# design.net
KiCad netlist of a schematic drawn in Altium Designer
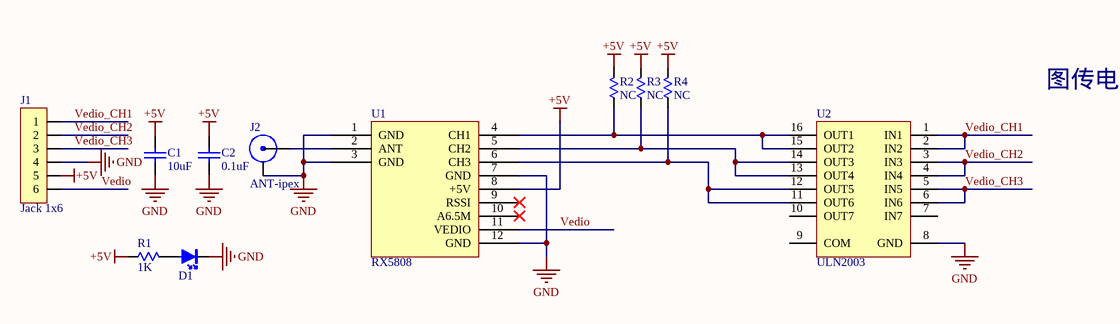
[diagram p0: 海关全向控制器图传转接板.SchDoc]

(export (version "E")
  (design (tool "Eeschema 10.0.6"))
  (components
    (comp (ref "C1") (value "10uF") (footprint "C0603") (libsource (lib "SMD") (part "Cap Semi")))
    (comp (ref "C2") (value "0.1uF") (footprint "C0603") (libsource (lib "SMD") (part "Cap Semi")))
    (comp (ref "D1")
      (value "LED")
      (footprint "LED0603")
      (libsource (lib "Passive Components Class") (part "LED"))
    )
    (comp (ref "J1")
      (value "Jack 1x6")
      (footprint "ZH-6AWD")
      (description "插座")
      (libsource (lib "Connector") (part "Jack 1x6"))
    )
    (comp (ref "J2") (value "ANT-ipex") (footprint "IPEX") (libsource (lib "RLCYDF") (part "ANT-ipex")))
    (comp (ref "R1")
      (value "1K")
      (footprint "R0603")
      (description "Resistor")
      (fields (field (name "PUBLISHER") "Altium Limited"))
      (libsource (lib "UP-Robot") (part "Res"))
    )
    (comp (ref "R2")
      (value "NC")
      (footprint "R0603")
      (description "Resistor")
      (fields (field (name "PUBLISHER") "Altium Limited"))
      (libsource (lib "UP-Robot") (part "Res"))
    )
    (comp (ref "R3")
      (value "NC")
      (footprint "R0603")
      (description "Resistor")
      (fields (field (name "PUBLISHER") "Altium Limited"))
      (libsource (lib "UP-Robot") (part "Res"))
    )
    (comp (ref "R4")
      (value "NC")
      (footprint "R0603")
      (description "Resistor")
      (fields (field (name "PUBLISHER") "Altium Limited"))
      (libsource (lib "UP-Robot") (part "Res"))
    )
    (comp (ref "U1") (value "RX5808") (footprint "RX5808") (libsource (lib "Module") (part "RX5808")))
    (comp (ref "U2") (value "ULN2003") (footprint "SO16") (libsource (lib "Logic Class") (part "ULN2003")))
  )
  (nets
    (net (code "1") (name "+5V") (class "Default")
      (node (ref "C1") (pin "2") (pinfunction "2_2") (pintype "passive"))
      (node (ref "C2") (pin "2") (pinfunction "2_2") (pintype "passive"))
      (node (ref "J1") (pin "5") (pinfunction "5_5") (pintype "passive"))
      (node (ref "R1") (pin "1") (pinfunction "1_1") (pintype "passive"))
      (node (ref "R2") (pin "2") (pinfunction "2_2") (pintype "passive"))
      (node (ref "R3") (pin "2") (pinfunction "2_2") (pintype "passive"))
      (node (ref "R4") (pin "2") (pinfunction "2_2") (pintype "passive"))
      (node (ref "U1") (pin "8") (pinfunction "+5V_8") (pintype "passive"))
    )
    (net (code "2") (name "/Vedio") (class "Default")
      (node (ref "J1") (pin "6") (pinfunction "6_6") (pintype "passive"))
      (node (ref "U1") (pin "11") (pinfunction "VEDIO_11") (pintype "passive"))
    )
    (net (code "3") (name "/Vedio_CH1") (class "Default")
      (node (ref "J1") (pin "1") (pinfunction "1_1") (pintype "passive"))
      (node (ref "U2") (pin "1") (pinfunction "IN1_1") (pintype "passive"))
      (node (ref "U2") (pin "2") (pinfunction "IN2_2") (pintype "passive"))
    )
    (net (code "4") (name "/Vedio_CH2") (class "Default")
      (node (ref "J1") (pin "2") (pinfunction "2_2") (pintype "passive"))
      (node (ref "U2") (pin "3") (pinfunction "IN3_3") (pintype "passive"))
      (node (ref "U2") (pin "4") (pinfunction "IN4_4") (pintype "passive"))
    )
    (net (code "5") (name "/Vedio_CH3") (class "Default")
      (node (ref "J1") (pin "3") (pinfunction "3_3") (pintype "passive"))
      (node (ref "U2") (pin "5") (pinfunction "IN5_5") (pintype "passive"))
      (node (ref "U2") (pin "6") (pinfunction "IN6_6") (pintype "passive"))
    )
    (net (code "6") (name "GND") (class "Default")
      (node (ref "C1") (pin "1") (pinfunction "1_1") (pintype "passive"))
      (node (ref "C2") (pin "1") (pinfunction "1_1") (pintype "passive"))
      (node (ref "D1") (pin "2") (pinfunction "K_2") (pintype "passive"))
      (node (ref "J1") (pin "4") (pinfunction "4_4") (pintype "passive"))
      (node (ref "J2") (pin "2") (pinfunction "GND_2") (pintype "passive"))
      (node (ref "U1") (pin "1") (pinfunction "GND_1") (pintype "passive"))
      (node (ref "U1") (pin "12") (pinfunction "GND_12") (pintype "passive"))
      (node (ref "U1") (pin "3") (pinfunction "GND_3") (pintype "passive"))
      (node (ref "U1") (pin "7") (pinfunction "GND_7") (pintype "passive"))
      (node (ref "U2") (pin "8") (pinfunction "GND_8") (pintype "power_in"))
    )
    (net (code "7") (name "Net-(D1-A)") (class "Default")
      (node (ref "D1") (pin "1") (pinfunction "A_1") (pintype "passive"))
      (node (ref "R1") (pin "2") (pinfunction "2_2") (pintype "passive"))
    )
    (net (code "8") (name "Net-(J2-ANT)") (class "Default")
      (node (ref "J2") (pin "1") (pinfunction "ANT_1") (pintype "passive"))
      (node (ref "U1") (pin "2") (pinfunction "ANT_2") (pintype "passive"))
    )
    (net (code "9") (name "Net-(U1-CH1)") (class "Default")
      (node (ref "R2") (pin "1") (pinfunction "1_1") (pintype "passive"))
      (node (ref "U1") (pin "4") (pinfunction "CH1_4") (pintype "passive"))
      (node (ref "U2") (pin "15") (pinfunction "OUT2_15") (pintype "open_collector"))
      (node (ref "U2") (pin "16") (pinfunction "OUT1_16") (pintype "open_collector"))
    )
    (net (code "10") (name "Net-(U1-CH2)") (class "Default")
      (node (ref "R3") (pin "1") (pinfunction "1_1") (pintype "passive"))
      (node (ref "U1") (pin "5") (pinfunction "CH2_5") (pintype "passive"))
      (node (ref "U2") (pin "13") (pinfunction "OUT4_13") (pintype "open_collector"))
      (node (ref "U2") (pin "14") (pinfunction "OUT3_14") (pintype "open_collector"))
    )
    (net (code "11") (name "Net-(U1-CH3)") (class "Default")
      (node (ref "R4") (pin "1") (pinfunction "1_1") (pintype "passive"))
      (node (ref "U1") (pin "6") (pinfunction "CH3_6") (pintype "passive"))
      (node (ref "U2") (pin "11") (pinfunction "OUT6_11") (pintype "open_collector"))
      (node (ref "U2") (pin "12") (pinfunction "OUT5_12") (pintype "open_collector"))
    )
    (net (code "12") (name "unconnected-(U1-A6.5M-Pad10)") (class "Default")
      (node (ref "U1") (pin "10") (pinfunction "A6.5M_10") (pintype "passive+no_connect"))
    )
    (net (code "13") (name "unconnected-(U1-RSSI-Pad9)") (class "Default")
      (node (ref "U1") (pin "9") (pinfunction "RSSI_9") (pintype "passive+no_connect"))
    )
    (net (code "14") (name "unconnected-(U2-COM-Pad9)") (class "Default")
      (node (ref "U2") (pin "9") (pinfunction "COM_9") (pintype "passive"))
    )
    (net (code "15") (name "unconnected-(U2-IN7-Pad7)") (class "Default")
      (node (ref "U2") (pin "7") (pinfunction "IN7_7") (pintype "passive"))
    )
    (net (code "16") (name "unconnected-(U2-OUT7-Pad10)") (class "Default")
      (node (ref "U2") (pin "10") (pinfunction "OUT7_10") (pintype "open_collector"))
    )
  )
)
